# TLV5617_yusnows.net
KiCad netlist of a schematic drawn in Altium Designer
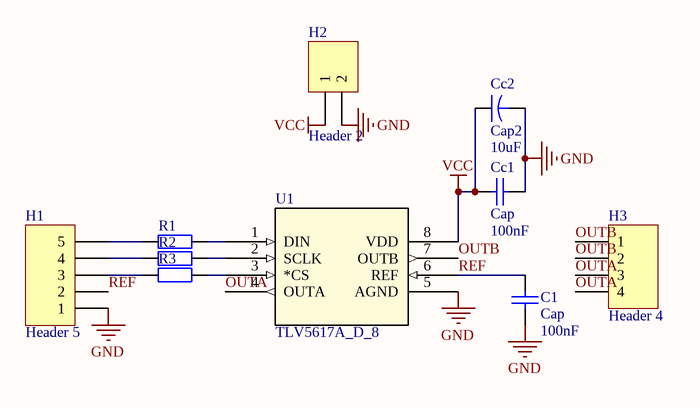
[diagram p0: TLV5617_yusnows.SchDoc]

(export (version "E")
  (design (tool "Eeschema 10.0.6"))
  (components
    (comp (ref "C1")
      (value "Cap")
      (footprint "0805C")
      (description "Capacitor")
      (fields (field (name "ALTIUM_VALUE") "100nF") (field (name "PUBLISHER") "Altium Limited"))
      (libsource (lib "Miscellaneous Devices") (part "Cap"))
    )
    (comp (ref "Cc1")
      (value "Cap")
      (footprint "0805C")
      (description "Capacitor")
      (fields (field (name "ALTIUM_VALUE") "100nF") (field (name "PUBLISHER") "Altium Limited"))
      (libsource (lib "Miscellaneous Devices") (part "Cap"))
    )
    (comp (ref "Cc2")
      (value "Cap2")
      (footprint "CAP_SMD_3216")
      (description "Capacitor")
      (fields (field (name "ALTIUM_VALUE") "10uF") (field (name "PUBLISHER") "Altium Limited"))
      (libsource (lib "Miscellaneous Devices") (part "Cap2"))
    )
    (comp (ref "H1")
      (value "Header 5")
      (footprint "HDR1X5")
      (description "Header, 5-Pin")
      (fields (field (name "PUBLISHER") "Altium Limited"))
      (libsource (lib "Miscellaneous Connectors") (part "Header 5"))
    )
    (comp (ref "H2")
      (value "Header 2")
      (footprint "HDR1X2")
      (description "Header, 2-Pin")
      (fields (field (name "PUBLISHER") "Altium Limited"))
      (libsource (lib "Miscellaneous Connectors") (part "Header 2"))
    )
    (comp (ref "H3")
      (value "Header 4")
      (footprint "HDR1X4")
      (description "Header, 4-Pin")
      (fields (field (name "PUBLISHER") "Altium Limited"))
      (libsource (lib "Miscellaneous Connectors") (part "Header 4"))
    )
    (comp (ref "R1")
      (value "Rin1")
      (footprint "0805R")
      (description "Resistor")
      (fields (field (name "PUBLISHER") "Altium Limited"))
      (libsource (lib "Miscellaneous Devices") (part "Res2"))
    )
    (comp (ref "R2")
      (value "Rin1")
      (footprint "0805R")
      (description "Resistor")
      (fields (field (name "PUBLISHER") "Altium Limited"))
      (libsource (lib "Miscellaneous Devices") (part "Res2"))
    )
    (comp (ref "R3")
      (value "Rin1")
      (footprint "0805R")
      (description "Resistor")
      (fields (field (name "PUBLISHER") "Altium Limited"))
      (libsource (lib "Miscellaneous Devices") (part "Res2"))
    )
    (comp (ref "U1")
      (value "TLV5617A_D_8")
      (footprint "D8")
      (description "Imported")
      (fields
        (field (name "MANUFACTURER_PART_NUMBER") "tlv5617a_d_8")
        (field (name "GENERIC_PART_NUMBER") "TLV5617A")
      )
      (libsource (lib "TLV5617") (part "TLV5617A_D_8"))
    )
  )
  (nets
    (net (code "1") (name "/OUTA") (class "Default")
      (node (ref "H3") (pin "3") (pinfunction "3_3") (pintype "passive"))
      (node (ref "H3") (pin "4") (pinfunction "4_4") (pintype "passive"))
      (node (ref "U1") (pin "4") (pinfunction "OUTA_4") (pintype "output"))
    )
    (net (code "2") (name "/OUTB") (class "Default")
      (node (ref "H3") (pin "1") (pinfunction "1_1") (pintype "passive"))
      (node (ref "H3") (pin "2") (pinfunction "2_2") (pintype "passive"))
      (node (ref "U1") (pin "7") (pinfunction "OUTB_7") (pintype "output"))
    )
    (net (code "3") (name "/REF") (class "Default")
      (node (ref "C1") (pin "1") (pinfunction "1_1") (pintype "passive"))
      (node (ref "H1") (pin "2") (pinfunction "2_2") (pintype "passive"))
      (node (ref "U1") (pin "6") (pinfunction "REF_6") (pintype "input"))
    )
    (net (code "4") (name "GND") (class "Default")
      (node (ref "C1") (pin "2") (pinfunction "2_2") (pintype "passive"))
      (node (ref "Cc1") (pin "1") (pinfunction "1_1") (pintype "passive"))
      (node (ref "Cc2") (pin "2") (pinfunction "2_2") (pintype "passive"))
      (node (ref "H1") (pin "1") (pinfunction "1_1") (pintype "passive"))
      (node (ref "H2") (pin "2") (pinfunction "2_2") (pintype "passive"))
      (node (ref "U1") (pin "5") (pinfunction "AGND_5") (pintype "power_in"))
    )
    (net (code "5") (name "Net-(H1-Pad3)") (class "Default")
      (node (ref "H1") (pin "3") (pinfunction "3_3") (pintype "passive"))
      (node (ref "R3") (pin "1") (pinfunction "1_1") (pintype "passive"))
    )
    (net (code "6") (name "Net-(H1-Pad4)") (class "Default")
      (node (ref "H1") (pin "4") (pinfunction "4_4") (pintype "passive"))
      (node (ref "R2") (pin "1") (pinfunction "1_1") (pintype "passive"))
    )
    (net (code "7") (name "Net-(H1-Pad5)") (class "Default")
      (node (ref "H1") (pin "5") (pinfunction "5_5") (pintype "passive"))
      (node (ref "R1") (pin "1") (pinfunction "1_1") (pintype "passive"))
    )
    (net (code "8") (name "Net-(U1-*CS)") (class "Default")
      (node (ref "R3") (pin "2") (pinfunction "2_2") (pintype "passive"))
      (node (ref "U1") (pin "3") (pinfunction "*CS_3") (pintype "input"))
    )
    (net (code "9") (name "Net-(U1-DIN)") (class "Default")
      (node (ref "R1") (pin "2") (pinfunction "2_2") (pintype "passive"))
      (node (ref "U1") (pin "1") (pinfunction "DIN_1") (pintype "input"))
    )
    (net (code "10") (name "Net-(U1-SCLK)") (class "Default")
      (node (ref "R2") (pin "2") (pinfunction "2_2") (pintype "passive"))
      (node (ref "U1") (pin "2") (pinfunction "SCLK_2") (pintype "input"))
    )
    (net (code "11") (name "VCC") (class "Default")
      (node (ref "Cc1") (pin "2") (pinfunction "2_2") (pintype "passive"))
      (node (ref "Cc2") (pin "1") (pinfunction "1_1") (pintype "passive"))
      (node (ref "H2") (pin "1") (pinfunction "1_1") (pintype "passive"))
      (node (ref "U1") (pin "8") (pinfunction "VDD_8") (pintype "power_in"))
    )
  )
)
